# power_supply.net
KiCad netlist of a schematic drawn in Altium Designer
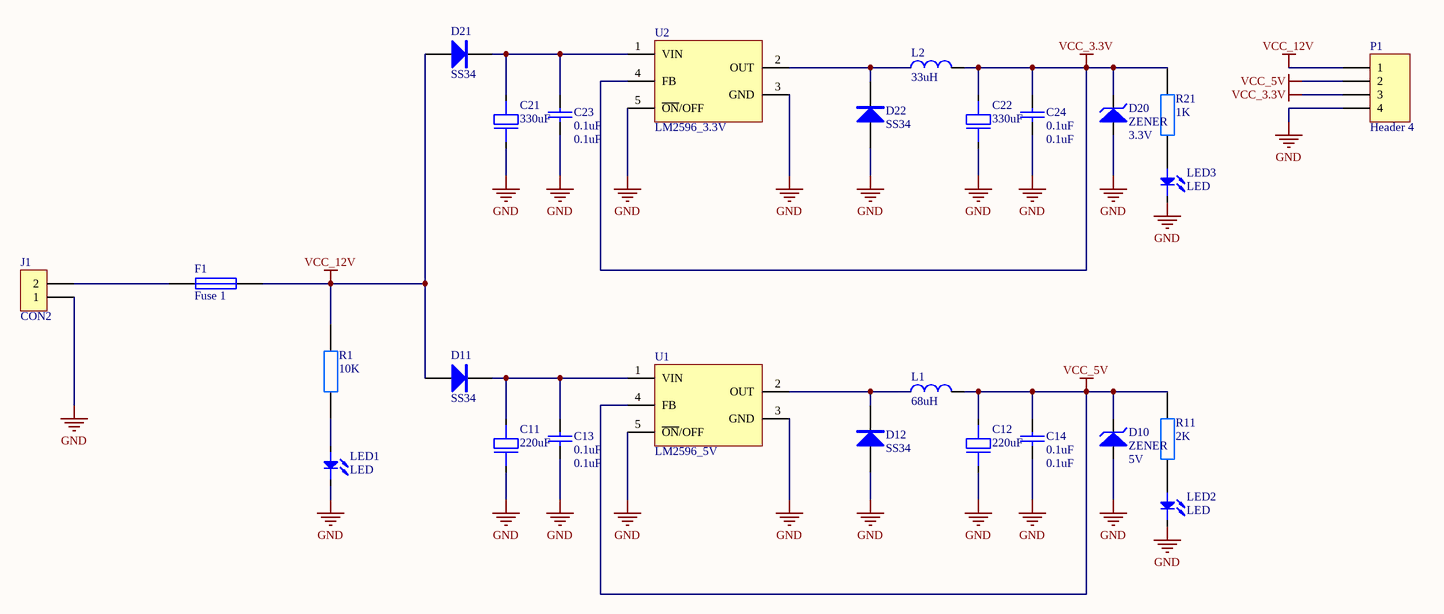
[diagram p0: power supply.SchDoc]

(export (version "E")
  (design (tool "Eeschema 10.0.6"))
  (components
    (comp (ref "C11")
      (value "220uF")
      (footprint "SMD-EC-F10")
      (libsource (lib "common") (part "Electrolytic CAP"))
    )
    (comp (ref "C12")
      (value "220uF")
      (footprint "SMD-EC-F10")
      (libsource (lib "common") (part "Electrolytic CAP"))
    )
    (comp (ref "C13")
      (value "0.1uF")
      (footprint "0805C")
      (fields (field (name "ALTIUM_VALUE") "0.1uF"))
      (libsource (lib "common") (part "CAP"))
    )
    (comp (ref "C14")
      (value "0.1uF")
      (footprint "0805C")
      (fields (field (name "ALTIUM_VALUE") "0.1uF"))
      (libsource (lib "common") (part "CAP"))
    )
    (comp (ref "C21")
      (value "330uF")
      (footprint "SMD-EC-F10")
      (libsource (lib "common") (part "Electrolytic CAP"))
    )
    (comp (ref "C22")
      (value "330uF")
      (footprint "SMD-EC-F10")
      (libsource (lib "common") (part "Electrolytic CAP"))
    )
    (comp (ref "C23")
      (value "0.1uF")
      (footprint "0805C")
      (fields (field (name "ALTIUM_VALUE") "0.1uF"))
      (libsource (lib "common") (part "CAP"))
    )
    (comp (ref "C24")
      (value "0.1uF")
      (footprint "0805C")
      (fields (field (name "ALTIUM_VALUE") "0.1uF"))
      (libsource (lib "common") (part "CAP"))
    )
    (comp (ref "D10")
      (value "ZENER")
      (footprint "1206D")
      (fields (field (name "ALTIUM_VALUE") "5V"))
      (libsource (lib "common") (part "ZENER"))
    )
    (comp (ref "D11")
      (value "SS34")
      (footprint "SMA")
      (description "Diode")
      (libsource (lib "common") (part "SS14"))
    )
    (comp (ref "D12")
      (value "SS34")
      (footprint "SMA")
      (description "Diode")
      (libsource (lib "common") (part "SS14"))
    )
    (comp (ref "D20")
      (value "ZENER")
      (footprint "1206D")
      (fields (field (name "ALTIUM_VALUE") "3.3V"))
      (libsource (lib "common") (part "ZENER"))
    )
    (comp (ref "D21")
      (value "SS34")
      (footprint "SMA")
      (description "Diode")
      (libsource (lib "common") (part "SS14"))
    )
    (comp (ref "D22")
      (value "SS34")
      (footprint "SMA")
      (description "Diode")
      (libsource (lib "common") (part "SS14"))
    )
    (comp (ref "F1")
      (value "Fuse 1")
      (footprint "FUSE1")
      (description "Fuse")
      (fields (field (name "PUBLISHER") "Altium Limited"))
      (libsource (lib "common") (part "Fuse 1"))
    )
    (comp (ref "J1") (value "CON2") (footprint "con2") (libsource (lib "common") (part "CON2")))
    (comp (ref "L1") (value "68uH") (footprint "12x12") (libsource (lib "common") (part "Inductance")))
    (comp (ref "L2") (value "33uH") (footprint "12x12") (libsource (lib "common") (part "Inductance")))
    (comp (ref "LED1") (value "LED") (footprint "3528 led") (libsource (lib "common") (part "LED")))
    (comp (ref "LED2") (value "LED") (footprint "3528 led") (libsource (lib "common") (part "LED")))
    (comp (ref "LED3") (value "LED") (footprint "3528 led") (libsource (lib "common") (part "LED")))
    (comp (ref "P1")
      (value "Header 4")
      (footprint "HDR1X4")
      (description "Header, 4-Pin")
      (fields (field (name "PUBLISHER") "Altium Limited"))
      (libsource (lib "Miscellaneous Connectors") (part "Header 4"))
    )
    (comp (ref "R1")
      (value "10K")
      (footprint "0805")
      (description "RES")
      (libsource (lib "common") (part "RES"))
    )
    (comp (ref "R11")
      (value "2K")
      (footprint "0805")
      (description "RES")
      (libsource (lib "common") (part "RES"))
    )
    (comp (ref "R21")
      (value "1K")
      (footprint "0805")
      (description "RES")
      (libsource (lib "common") (part "RES"))
    )
    (comp (ref "U1")
      (value "LM2596_5V")
      (footprint "平面IC:TO-263")
      (description "IC-power")
      (libsource (lib "common") (part "LM2596"))
    )
    (comp (ref "U2")
      (value "LM2596_3.3V")
      (footprint "平面IC:to-263")
      (description "IC-power")
      (libsource (lib "common") (part "LM2596"))
    )
  )
  (nets
    (net (code "1") (name "GND") (class "Default")
      (node (ref "C11") (pin "2") (pinfunction "2_2") (pintype "passive"))
      (node (ref "C12") (pin "2") (pinfunction "2_2") (pintype "passive"))
      (node (ref "C13") (pin "2") (pinfunction "2_2") (pintype "passive"))
      (node (ref "C14") (pin "2") (pinfunction "2_2") (pintype "passive"))
      (node (ref "C21") (pin "2") (pinfunction "2_2") (pintype "passive"))
      (node (ref "C22") (pin "2") (pinfunction "2_2") (pintype "passive"))
      (node (ref "C23") (pin "2") (pinfunction "2_2") (pintype "passive"))
      (node (ref "C24") (pin "2") (pinfunction "2_2") (pintype "passive"))
      (node (ref "D10") (pin "1") (pinfunction "A_1") (pintype "passive"))
      (node (ref "D12") (pin "1") (pinfunction "A_1") (pintype "passive"))
      (node (ref "D20") (pin "1") (pinfunction "A_1") (pintype "passive"))
      (node (ref "D22") (pin "1") (pinfunction "A_1") (pintype "passive"))
      (node (ref "J1") (pin "1") (pinfunction "1_1") (pintype "passive"))
      (node (ref "LED1") (pin "2") (pintype "passive"))
      (node (ref "LED2") (pin "2") (pintype "passive"))
      (node (ref "LED3") (pin "2") (pintype "passive"))
      (node (ref "P1") (pin "4") (pinfunction "4_4") (pintype "passive"))
      (node (ref "U1") (pin "3") (pinfunction "GND_3") (pintype "passive"))
      (node (ref "U1") (pin "5") (pinfunction "~{ON}/OFF_5") (pintype "passive"))
      (node (ref "U2") (pin "3") (pinfunction "GND_3") (pintype "passive"))
      (node (ref "U2") (pin "5") (pinfunction "~{ON}/OFF_5") (pintype "passive"))
    )
    (net (code "2") (name "Net-(D11-K)") (class "Default")
      (node (ref "C11") (pin "1") (pinfunction "1_1") (pintype "passive"))
      (node (ref "C13") (pin "1") (pinfunction "1_1") (pintype "passive"))
      (node (ref "D11") (pin "2") (pinfunction "K_2") (pintype "passive"))
      (node (ref "U1") (pin "1") (pinfunction "VIN_1") (pintype "passive"))
    )
    (net (code "3") (name "Net-(D12-K)") (class "Default")
      (node (ref "D12") (pin "2") (pinfunction "K_2") (pintype "passive"))
      (node (ref "L1") (pin "2") (pinfunction "2_2") (pintype "passive"))
      (node (ref "U1") (pin "2") (pinfunction "OUT_2") (pintype "passive"))
    )
    (net (code "4") (name "Net-(D21-K)") (class "Default")
      (node (ref "C21") (pin "1") (pinfunction "1_1") (pintype "passive"))
      (node (ref "C23") (pin "1") (pinfunction "1_1") (pintype "passive"))
      (node (ref "D21") (pin "2") (pinfunction "K_2") (pintype "passive"))
      (node (ref "U2") (pin "1") (pinfunction "VIN_1") (pintype "passive"))
    )
    (net (code "5") (name "Net-(D22-K)") (class "Default")
      (node (ref "D22") (pin "2") (pinfunction "K_2") (pintype "passive"))
      (node (ref "L2") (pin "2") (pinfunction "2_2") (pintype "passive"))
      (node (ref "U2") (pin "2") (pinfunction "OUT_2") (pintype "passive"))
    )
    (net (code "6") (name "Net-(F1-Pad1)") (class "Default")
      (node (ref "F1") (pin "1") (pinfunction "1_1") (pintype "passive"))
      (node (ref "J1") (pin "2") (pinfunction "2_2") (pintype "passive"))
    )
    (net (code "7") (name "Net-(LED1-Pad1)") (class "Default")
      (node (ref "LED1") (pin "1") (pintype "passive"))
      (node (ref "R1") (pin "1") (pinfunction "1_1") (pintype "passive"))
    )
    (net (code "8") (name "Net-(LED2-Pad1)") (class "Default")
      (node (ref "LED2") (pin "1") (pintype "passive"))
      (node (ref "R11") (pin "1") (pinfunction "1_1") (pintype "passive"))
    )
    (net (code "9") (name "Net-(LED3-Pad1)") (class "Default")
      (node (ref "LED3") (pin "1") (pintype "passive"))
      (node (ref "R21") (pin "1") (pinfunction "1_1") (pintype "passive"))
    )
    (net (code "10") (name "VCC_3.3V") (class "Default")
      (node (ref "C22") (pin "1") (pinfunction "1_1") (pintype "passive"))
      (node (ref "C24") (pin "1") (pinfunction "1_1") (pintype "passive"))
      (node (ref "D20") (pin "2") (pinfunction "K_2") (pintype "passive"))
      (node (ref "L2") (pin "1") (pinfunction "1_1") (pintype "passive"))
      (node (ref "P1") (pin "3") (pinfunction "3_3") (pintype "passive"))
      (node (ref "R21") (pin "2") (pinfunction "2_2") (pintype "passive"))
      (node (ref "U2") (pin "4") (pinfunction "FB_4") (pintype "passive"))
    )
    (net (code "11") (name "VCC_5V") (class "Default")
      (node (ref "C12") (pin "1") (pinfunction "1_1") (pintype "passive"))
      (node (ref "C14") (pin "1") (pinfunction "1_1") (pintype "passive"))
      (node (ref "D10") (pin "2") (pinfunction "K_2") (pintype "passive"))
      (node (ref "L1") (pin "1") (pinfunction "1_1") (pintype "passive"))
      (node (ref "P1") (pin "2") (pinfunction "2_2") (pintype "passive"))
      (node (ref "R11") (pin "2") (pinfunction "2_2") (pintype "passive"))
      (node (ref "U1") (pin "4") (pinfunction "FB_4") (pintype "passive"))
    )
    (net (code "12") (name "VCC_12V") (class "Default")
      (node (ref "D11") (pin "1") (pinfunction "A_1") (pintype "passive"))
      (node (ref "D21") (pin "1") (pinfunction "A_1") (pintype "passive"))
      (node (ref "F1") (pin "2") (pinfunction "2_2") (pintype "passive"))
      (node (ref "P1") (pin "1") (pinfunction "1_1") (pintype "passive"))
      (node (ref "R1") (pin "2") (pinfunction "2_2") (pintype "passive"))
    )
  )
)
